# 05-LVDS_RGB.net
KiCad netlist of a schematic drawn in Altium Designer
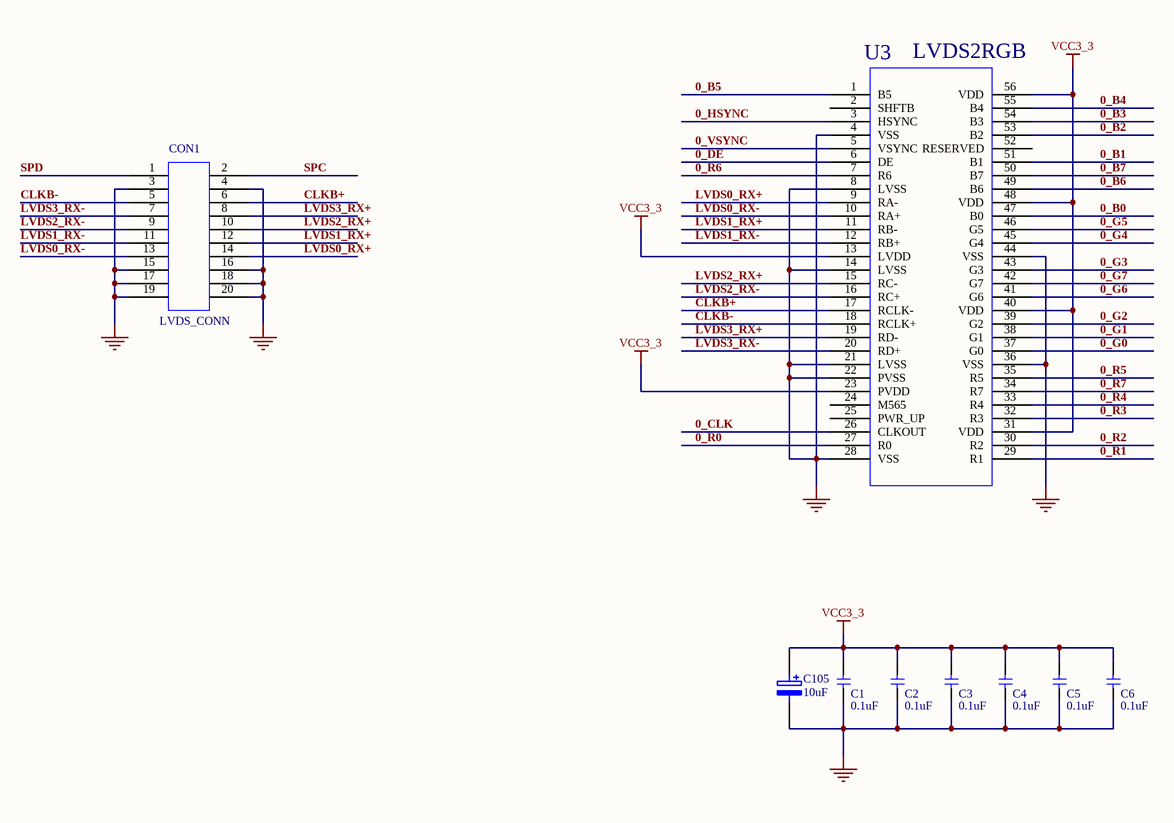
[diagram p0: 05-LVDS_RGB.SchDoc]

(export (version "E")
  (design (tool "Eeschema 10.0.6"))
  (components
    (comp (ref "C1")
      (value "0.1uF")
      (footprint "C0603")
      (fields (field (name "VOLTAGE") "CMAX") (field (name "Comment") "C_2"))
      (libsource (lib "VIDEO_Demo_Kit_1") (part "C_2"))
    )
    (comp (ref "C2")
      (value "0.1uF")
      (footprint "C0603")
      (fields (field (name "VOLTAGE") "CMAX") (field (name "Comment") "C_2"))
      (libsource (lib "VIDEO_Demo_Kit_1") (part "C_2"))
    )
    (comp (ref "C3")
      (value "0.1uF")
      (footprint "C0603")
      (fields (field (name "VOLTAGE") "CMAX") (field (name "Comment") "C_2"))
      (libsource (lib "VIDEO_Demo_Kit_1") (part "C_2"))
    )
    (comp (ref "C4")
      (value "0.1uF")
      (footprint "C0603")
      (fields (field (name "VOLTAGE") "CMAX") (field (name "Comment") "C_2"))
      (libsource (lib "VIDEO_Demo_Kit_1") (part "C_2"))
    )
    (comp (ref "C5")
      (value "0.1uF")
      (footprint "C0603")
      (fields (field (name "VOLTAGE") "CMAX") (field (name "Comment") "C_2"))
      (libsource (lib "VIDEO_Demo_Kit_1") (part "C_2"))
    )
    (comp (ref "C6")
      (value "0.1uF")
      (footprint "C0603")
      (fields (field (name "VOLTAGE") "CMAX") (field (name "Comment") "C_2"))
      (libsource (lib "VIDEO_Demo_Kit_1") (part "C_2"))
    )
    (comp (ref "C105")
      (value "10uF")
      (footprint "3528-C")
      (description "Electrolytic Capacitor")
      (libsource (lib "*") (part "ELECTRO2"))
    )
    (comp (ref "CON1")
      (value "LVDS_CONN")
      (footprint "JTAG-20X2.54")
      (fields (field (name "Comment") "CON20A"))
      (libsource (lib "VIDEO_Demo_Kit_1") (part "CON20A"))
    )
    (comp (ref "U3")
      (value "LVDS2RGB")
      (footprint "TSSOP56")
      (fields (field (name "Comment") "EP102"))
      (libsource (lib "*") (part "EP102"))
    )
  )
  (nets
    (net (code "1") (name "/0_B0") (class "Default")
      (node (ref "U3") (pin "47") (pinfunction "B0_47") (pintype "passive"))
    )
    (net (code "2") (name "/0_B1") (class "Default")
      (node (ref "U3") (pin "51") (pinfunction "B1_51") (pintype "passive"))
    )
    (net (code "3") (name "/0_B2") (class "Default")
      (node (ref "U3") (pin "53") (pinfunction "B2_53") (pintype "passive"))
    )
    (net (code "4") (name "/0_B3") (class "Default")
      (node (ref "U3") (pin "54") (pinfunction "B3_54") (pintype "passive"))
    )
    (net (code "5") (name "/0_B4") (class "Default")
      (node (ref "U3") (pin "55") (pinfunction "B4_55") (pintype "passive"))
    )
    (net (code "6") (name "/0_B5") (class "Default")
      (node (ref "U3") (pin "1") (pinfunction "B5_1") (pintype "passive"))
    )
    (net (code "7") (name "/0_B6") (class "Default")
      (node (ref "U3") (pin "49") (pinfunction "B6_49") (pintype "passive"))
    )
    (net (code "8") (name "/0_B7") (class "Default")
      (node (ref "U3") (pin "50") (pinfunction "B7_50") (pintype "passive"))
    )
    (net (code "9") (name "/0_CLK") (class "Default")
      (node (ref "U3") (pin "26") (pinfunction "CLKOUT_26") (pintype "passive"))
    )
    (net (code "10") (name "/0_DE") (class "Default")
      (node (ref "U3") (pin "6") (pinfunction "DE_6") (pintype "passive"))
    )
    (net (code "11") (name "/0_G0") (class "Default")
      (node (ref "U3") (pin "37") (pinfunction "G0_37") (pintype "passive"))
    )
    (net (code "12") (name "/0_G1") (class "Default")
      (node (ref "U3") (pin "38") (pinfunction "G1_38") (pintype "passive"))
    )
    (net (code "13") (name "/0_G2") (class "Default")
      (node (ref "U3") (pin "39") (pinfunction "G2_39") (pintype "passive"))
    )
    (net (code "14") (name "/0_G3") (class "Default")
      (node (ref "U3") (pin "43") (pinfunction "G3_43") (pintype "passive"))
    )
    (net (code "15") (name "/0_G4") (class "Default")
      (node (ref "U3") (pin "45") (pinfunction "G4_45") (pintype "passive"))
    )
    (net (code "16") (name "/0_G5") (class "Default")
      (node (ref "U3") (pin "46") (pinfunction "G5_46") (pintype "passive"))
    )
    (net (code "17") (name "/0_G6") (class "Default")
      (node (ref "U3") (pin "41") (pinfunction "G6_41") (pintype "passive"))
    )
    (net (code "18") (name "/0_G7") (class "Default")
      (node (ref "U3") (pin "42") (pinfunction "G7_42") (pintype "passive"))
    )
    (net (code "19") (name "/0_HSYNC") (class "Default")
      (node (ref "U3") (pin "3") (pinfunction "HSYNC_3") (pintype "passive"))
    )
    (net (code "20") (name "/0_R0") (class "Default")
      (node (ref "U3") (pin "27") (pinfunction "R0_27") (pintype "passive"))
    )
    (net (code "21") (name "/0_R1") (class "Default")
      (node (ref "U3") (pin "29") (pinfunction "R1_29") (pintype "passive"))
    )
    (net (code "22") (name "/0_R2") (class "Default")
      (node (ref "U3") (pin "30") (pinfunction "R2_30") (pintype "passive"))
    )
    (net (code "23") (name "/0_R3") (class "Default")
      (node (ref "U3") (pin "32") (pinfunction "R3_32") (pintype "passive"))
    )
    (net (code "24") (name "/0_R4") (class "Default")
      (node (ref "U3") (pin "33") (pinfunction "R4_33") (pintype "passive"))
    )
    (net (code "25") (name "/0_R5") (class "Default")
      (node (ref "U3") (pin "35") (pinfunction "R5_35") (pintype "passive"))
    )
    (net (code "26") (name "/0_R6") (class "Default")
      (node (ref "U3") (pin "7") (pinfunction "R6_7") (pintype "passive"))
    )
    (net (code "27") (name "/0_R7") (class "Default")
      (node (ref "U3") (pin "34") (pinfunction "R7_34") (pintype "passive"))
    )
    (net (code "28") (name "/0_VSYNC") (class "Default")
      (node (ref "U3") (pin "5") (pinfunction "VSYNC_5") (pintype "passive"))
    )
    (net (code "29") (name "/CLKB+") (class "Default")
      (node (ref "CON1") (pin "6") (pinfunction "6_6") (pintype "passive"))
      (node (ref "U3") (pin "17") (pinfunction "RCLK-_17") (pintype "passive"))
    )
    (net (code "30") (name "/CLKB-") (class "Default")
      (node (ref "CON1") (pin "5") (pinfunction "5_5") (pintype "passive"))
      (node (ref "U3") (pin "18") (pinfunction "RCLK+_18") (pintype "passive"))
    )
    (net (code "31") (name "/LVDS0_RX+") (class "Default")
      (node (ref "CON1") (pin "14") (pinfunction "14_14") (pintype "passive"))
      (node (ref "U3") (pin "9") (pinfunction "RA-_9") (pintype "passive"))
    )
    (net (code "32") (name "/LVDS0_RX-") (class "Default")
      (node (ref "CON1") (pin "13") (pinfunction "13_13") (pintype "passive"))
      (node (ref "U3") (pin "10") (pinfunction "RA+_10") (pintype "passive"))
    )
    (net (code "33") (name "/LVDS1_RX+") (class "Default")
      (node (ref "CON1") (pin "12") (pinfunction "12_12") (pintype "passive"))
      (node (ref "U3") (pin "11") (pinfunction "RB-_11") (pintype "passive"))
    )
    (net (code "34") (name "/LVDS1_RX-") (class "Default")
      (node (ref "CON1") (pin "11") (pinfunction "11_11") (pintype "passive"))
      (node (ref "U3") (pin "12") (pinfunction "RB+_12") (pintype "passive"))
    )
    (net (code "35") (name "/LVDS2_RX+") (class "Default")
      (node (ref "CON1") (pin "10") (pinfunction "10_10") (pintype "passive"))
      (node (ref "U3") (pin "15") (pinfunction "RC-_15") (pintype "passive"))
    )
    (net (code "36") (name "/LVDS2_RX-") (class "Default")
      (node (ref "CON1") (pin "9") (pinfunction "9_9") (pintype "passive"))
      (node (ref "U3") (pin "16") (pinfunction "RC+_16") (pintype "passive"))
    )
    (net (code "37") (name "/LVDS3_RX+") (class "Default")
      (node (ref "CON1") (pin "8") (pinfunction "8_8") (pintype "passive"))
      (node (ref "U3") (pin "19") (pinfunction "RD-_19") (pintype "passive"))
    )
    (net (code "38") (name "/LVDS3_RX-") (class "Default")
      (node (ref "CON1") (pin "7") (pinfunction "7_7") (pintype "passive"))
      (node (ref "U3") (pin "20") (pinfunction "RD+_20") (pintype "passive"))
    )
    (net (code "39") (name "/SPC") (class "Default")
      (node (ref "CON1") (pin "2") (pinfunction "2_2") (pintype "passive"))
    )
    (net (code "40") (name "/SPD") (class "Default")
      (node (ref "CON1") (pin "1") (pinfunction "1_1") (pintype "passive"))
    )
    (net (code "41") (name "GND") (class "Default")
      (node (ref "C1") (pin "1") (pinfunction "1_1") (pintype "passive"))
      (node (ref "C105") (pin "2") (pinfunction "2_2") (pintype "passive"))
      (node (ref "C2") (pin "1") (pinfunction "1_1") (pintype "passive"))
      (node (ref "C3") (pin "1") (pinfunction "1_1") (pintype "passive"))
      (node (ref "C4") (pin "1") (pinfunction "1_1") (pintype "passive"))
      (node (ref "C5") (pin "1") (pinfunction "1_1") (pintype "passive"))
      (node (ref "C6") (pin "1") (pinfunction "1_1") (pintype "passive"))
      (node (ref "CON1") (pin "15") (pinfunction "15_15") (pintype "passive"))
      (node (ref "CON1") (pin "16") (pinfunction "16_16") (pintype "passive"))
      (node (ref "CON1") (pin "17") (pinfunction "17_17") (pintype "passive"))
      (node (ref "CON1") (pin "18") (pinfunction "18_18") (pintype "passive"))
      (node (ref "CON1") (pin "19") (pinfunction "19_19") (pintype "passive"))
      (node (ref "CON1") (pin "20") (pinfunction "20_20") (pintype "passive"))
      (node (ref "CON1") (pin "3") (pinfunction "3_3") (pintype "passive"))
      (node (ref "CON1") (pin "4") (pinfunction "4_4") (pintype "passive"))
      (node (ref "U3") (pin "14") (pinfunction "LVSS_14") (pintype "passive"))
      (node (ref "U3") (pin "21") (pinfunction "LVSS_21") (pintype "passive"))
      (node (ref "U3") (pin "22") (pinfunction "PVSS_22") (pintype "passive"))
      (node (ref "U3") (pin "28") (pinfunction "VSS_28") (pintype "passive"))
      (node (ref "U3") (pin "36") (pinfunction "VSS_36") (pintype "passive"))
      (node (ref "U3") (pin "4") (pinfunction "VSS_4") (pintype "passive"))
      (node (ref "U3") (pin "44") (pinfunction "VSS_44") (pintype "passive"))
      (node (ref "U3") (pin "8") (pinfunction "LVSS_8") (pintype "passive"))
    )
    (net (code "42") (name "VCC3_3") (class "Default")
      (node (ref "C1") (pin "2") (pinfunction "2_2") (pintype "passive"))
      (node (ref "C105") (pin "1") (pinfunction "1_1") (pintype "passive"))
      (node (ref "C2") (pin "2") (pinfunction "2_2") (pintype "passive"))
      (node (ref "C3") (pin "2") (pinfunction "2_2") (pintype "passive"))
      (node (ref "C4") (pin "2") (pinfunction "2_2") (pintype "passive"))
      (node (ref "C5") (pin "2") (pinfunction "2_2") (pintype "passive"))
      (node (ref "C6") (pin "2") (pinfunction "2_2") (pintype "passive"))
      (node (ref "U3") (pin "13") (pinfunction "LVDD_13") (pintype "passive"))
      (node (ref "U3") (pin "23") (pinfunction "PVDD_23") (pintype "passive"))
      (node (ref "U3") (pin "31") (pinfunction "VDD_31") (pintype "passive"))
      (node (ref "U3") (pin "40") (pinfunction "VDD_40") (pintype "passive"))
      (node (ref "U3") (pin "48") (pinfunction "VDD_48") (pintype "passive"))
      (node (ref "U3") (pin "56") (pinfunction "VDD_56") (pintype "passive"))
    )
    (net (code "43") (name "unconnected-(U3-M565-Pad24)") (class "Default")
      (node (ref "U3") (pin "24") (pinfunction "M565_24") (pintype "passive"))
    )
    (net (code "44") (name "unconnected-(U3-PWR_UP-Pad25)") (class "Default")
      (node (ref "U3") (pin "25") (pinfunction "PWR_UP_25") (pintype "passive"))
    )
    (net (code "45") (name "unconnected-(U3-RESERVED-Pad52)") (class "Default")
      (node (ref "U3") (pin "52") (pinfunction "RESERVED_52") (pintype "passive"))
    )
    (net (code "46") (name "unconnected-(U3-SHFTB-Pad2)") (class "Default")
      (node (ref "U3") (pin "2") (pinfunction "SHFTB_2") (pintype "passive"))
    )
  )
)
